# HV_Sense.net
KiCad netlist of a schematic drawn in Altium Designer
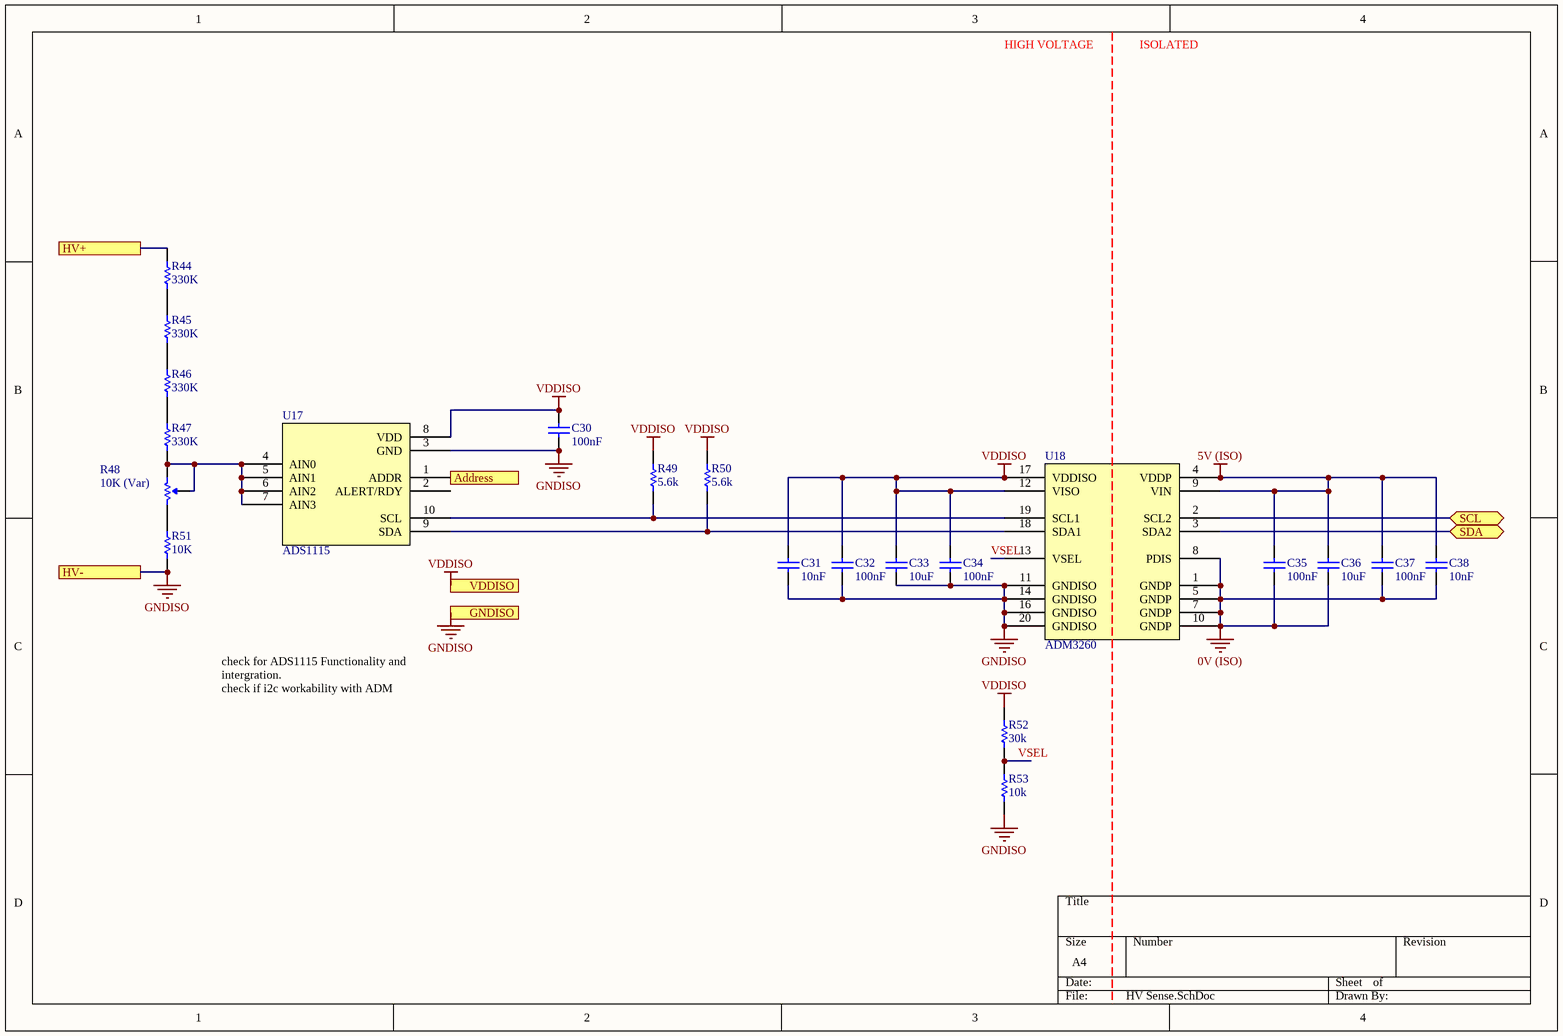
[diagram p0: HV Sense.SchDoc]

(export (version "E")
  (design (tool "Eeschema 10.0.6"))
  (components
    (comp (ref "C30")
      (value "100nF")
      (footprint "0805")
      (fields
        (field (name "PART NUMBER") "GCM21BR71H104KA37L")
        (field (name "TOLERANCE") "±10%")
        (field (name "MANUFACTURER") "muRata")
      )
      (libsource (lib "ts_20-standard-library") (part "Capacitor"))
    )
    (comp (ref "C31")
      (value "10nF")
      (footprint "0805")
      (fields
        (field (name "PART NUMBER") "GCM2195C1H103JA16D")
        (field (name "TOLERANCE") "±5%")
        (field (name "MANUFACTURER") "muRata")
      )
      (libsource (lib "ts_20-standard-library") (part "Capacitor"))
    )
    (comp (ref "C32")
      (value "100nF")
      (footprint "0805")
      (fields
        (field (name "PART NUMBER") "GCM21BR71H104KA37L")
        (field (name "TOLERANCE") "±10%")
        (field (name "MANUFACTURER") "muRata")
      )
      (libsource (lib "ts_20-standard-library") (part "Capacitor"))
    )
    (comp (ref "C33")
      (value "10uF")
      (footprint "0805")
      (fields
        (field (name "PART NUMBER") "GRM21BR6YA106KE43L")
        (field (name "TOLERANCE") "10%")
        (field (name "MANUFACTURER") "muRata")
      )
      (libsource (lib "ts_20-standard-library") (part "Capacitor"))
    )
    (comp (ref "C34")
      (value "100nF")
      (footprint "0805")
      (fields
        (field (name "PART NUMBER") "GCM21BR71H104KA37L")
        (field (name "TOLERANCE") "±10%")
        (field (name "MANUFACTURER") "muRata")
      )
      (libsource (lib "ts_20-standard-library") (part "Capacitor"))
    )
    (comp (ref "C35")
      (value "100nF")
      (footprint "0805")
      (fields
        (field (name "PART NUMBER") "GCM21BR71H104KA37L")
        (field (name "TOLERANCE") "±10%")
        (field (name "MANUFACTURER") "muRata")
      )
      (libsource (lib "ts_20-standard-library") (part "Capacitor"))
    )
    (comp (ref "C36")
      (value "10uF")
      (footprint "0805")
      (fields
        (field (name "PART NUMBER") "GRM21BR6YA106KE43L")
        (field (name "TOLERANCE") "10%")
        (field (name "MANUFACTURER") "muRata")
      )
      (libsource (lib "ts_20-standard-library") (part "Capacitor"))
    )
    (comp (ref "C37")
      (value "100nF")
      (footprint "0805")
      (fields
        (field (name "PART NUMBER") "GCM21BR71H104KA37L")
        (field (name "TOLERANCE") "±10%")
        (field (name "MANUFACTURER") "muRata")
      )
      (libsource (lib "ts_20-standard-library") (part "Capacitor"))
    )
    (comp (ref "C38")
      (value "10nF")
      (footprint "0805")
      (fields
        (field (name "PART NUMBER") "GCM2195C1H103JA16D")
        (field (name "TOLERANCE") "±5%")
        (field (name "MANUFACTURER") "muRata")
      )
      (libsource (lib "ts_20-standard-library") (part "Capacitor"))
    )
    (comp (ref "R44")
      (value "330K")
      (footprint "VB 0204")
      (fields
        (field (name "PART NUMBER") "MMA02040C3303FB300")
        (field (name "MANUFACTURER") "Vishay Beyschlag")
        (field (name "TOLERANCE") "0.01")
      )
      (libsource (lib "ts_20-standard-library") (part "Resistor"))
    )
    (comp (ref "R45")
      (value "330K")
      (footprint "VB 0204")
      (fields
        (field (name "PART NUMBER") "MMA02040C3303FB300")
        (field (name "MANUFACTURER") "Vishay Beyschlag")
        (field (name "TOLERANCE") "0.01")
      )
      (libsource (lib "ts_20-standard-library") (part "Resistor"))
    )
    (comp (ref "R46")
      (value "330K")
      (footprint "VB 0204")
      (fields
        (field (name "PART NUMBER") "MMA02040C3303FB300")
        (field (name "MANUFACTURER") "Vishay Beyschlag")
        (field (name "TOLERANCE") "0.01")
      )
      (libsource (lib "ts_20-standard-library") (part "Resistor"))
    )
    (comp (ref "R47")
      (value "330K")
      (footprint "VB 0204")
      (fields
        (field (name "PART NUMBER") "MMA02040C3303FB300")
        (field (name "MANUFACTURER") "Vishay Beyschlag")
        (field (name "TOLERANCE") "0.01")
      )
      (libsource (lib "ts_20-standard-library") (part "Resistor"))
    )
    (comp (ref "R48")
      (value "10K (Var)")
      (footprint "B 3296")
      (fields
        (field (name "PART NUMBER") "3296W-1-103LF")
        (field (name "MANUFACTURER") "Bournes Inc")
        (field (name "TOLERANCE") "0.1")
      )
      (libsource (lib "ts_20-standard-library") (part "Resistor (Potentiometer)"))
    )
    (comp (ref "R49")
      (value "5.6k")
      (footprint "0805")
      (fields
        (field (name "PART NUMBER") "RC0805FR075K6L")
        (field (name "MANUFACTURER") "YAGEO")
        (field (name "TOLERANCE") "0.01")
      )
      (libsource (lib "ts_20-standard-library") (part "Resistor"))
    )
    (comp (ref "R50")
      (value "5.6k")
      (footprint "0805")
      (fields
        (field (name "PART NUMBER") "RC0805FR075K6L")
        (field (name "MANUFACTURER") "YAGEO")
        (field (name "TOLERANCE") "0.01")
      )
      (libsource (lib "ts_20-standard-library") (part "Resistor"))
    )
    (comp (ref "R51")
      (value "10K")
      (footprint "VB 0204")
      (fields
        (field (name "PART NUMBER") "MMA02040C1002FB300")
        (field (name "MANUFACTURER") "Vishay Beyschlag")
        (field (name "TOLERANCE") "0.01")
      )
      (libsource (lib "ts_20-standard-library") (part "Resistor"))
    )
    (comp (ref "R52")
      (value "30k")
      (footprint "0805")
      (fields
        (field (name "PART NUMBER") "RC0805FR0730KL")
        (field (name "MANUFACTURER") "YAGEO")
        (field (name "TOLERANCE") "0.01")
      )
      (libsource (lib "ts_20-standard-library") (part "Resistor"))
    )
    (comp (ref "R53")
      (value "10k")
      (footprint "0805")
      (fields
        (field (name "PART NUMBER") "RC0805FR0710KL")
        (field (name "MANUFACTURER") "YAGEO")
        (field (name "TOLERANCE") "0.01")
      )
      (libsource (lib "ts_20-standard-library") (part "Resistor"))
    )
    (comp (ref "U17")
      (value "ADS1115")
      (footprint "TI 10-VSSOP")
      (description "16 Bit Analog to Digital Converter 2, 4 Input 1 Sigma-Delta 10-VSSOP")
      (fields
        (field (name "MANUFACTURER") "Texas Instruments")
        (field (name "DIGIKEY PART NUMBER") "296-38849-1-ND")
      )
      (libsource (lib "ts_20-standard-library") (part "ADS1115"))
    )
    (comp (ref "U18")
      (value "ADM3260")
      (footprint "AD 20-SSOP")
      (description "I²C Digital Isolator 2500Vrms 2 Channel 25kV/µs CMTI 20-SSOP (0.209\", 5.30mm Width)")
      (fields
        (field (name "MANUFACTURER") "Analog Devices")
        (field (name "DIGIKEY PART NUMBER") "ADM3260ARSZ-RL7CT-ND")
      )
      (libsource (lib "ts_20-standard-library") (part "ADM3260"))
    )
  )
  (nets
    (net (code "1") (name "/Address") (class "Default")
      (node (ref "U17") (pin "1") (pinfunction "ADDR_1") (pintype "passive"))
    )
    (net (code "2") (name "/HV+") (class "Default")
      (node (ref "R44") (pin "2") (pinfunction "2_2") (pintype "passive"))
    )
    (net (code "3") (name "/SCL") (class "Default")
      (node (ref "U18") (pin "2") (pinfunction "SCL2_2") (pintype "passive"))
    )
    (net (code "4") (name "/SDA") (class "Default")
      (node (ref "U18") (pin "3") (pinfunction "SDA2_3") (pintype "passive"))
    )
    (net (code "5") (name "/VSEL") (class "Default")
      (node (ref "R52") (pin "1") (pinfunction "1_1") (pintype "passive"))
      (node (ref "R53") (pin "2") (pinfunction "2_2") (pintype "passive"))
      (node (ref "U18") (pin "13") (pinfunction "VSEL_13") (pintype "passive"))
    )
    (net (code "6") (name "0V (ISO)") (class "Default")
      (node (ref "C35") (pin "1") (pinfunction "1_1") (pintype "passive"))
      (node (ref "C36") (pin "1") (pinfunction "1_1") (pintype "passive"))
      (node (ref "C37") (pin "1") (pinfunction "1_1") (pintype "passive"))
      (node (ref "C38") (pin "1") (pinfunction "1_1") (pintype "passive"))
      (node (ref "U18") (pin "1") (pinfunction "GNDP_1") (pintype "passive"))
      (node (ref "U18") (pin "10") (pinfunction "GNDP_10") (pintype "passive"))
      (node (ref "U18") (pin "5") (pinfunction "GNDP_5") (pintype "passive"))
      (node (ref "U18") (pin "7") (pinfunction "GNDP_7") (pintype "passive"))
      (node (ref "U18") (pin "8") (pinfunction "PDIS_8") (pintype "passive"))
    )
    (net (code "7") (name "5V (ISO)") (class "Default")
      (node (ref "C35") (pin "2") (pinfunction "2_2") (pintype "passive"))
      (node (ref "C36") (pin "2") (pinfunction "2_2") (pintype "passive"))
      (node (ref "C37") (pin "2") (pinfunction "2_2") (pintype "passive"))
      (node (ref "C38") (pin "2") (pinfunction "2_2") (pintype "passive"))
      (node (ref "U18") (pin "4") (pinfunction "VDDP_4") (pintype "passive"))
      (node (ref "U18") (pin "9") (pinfunction "VIN_9") (pintype "passive"))
    )
    (net (code "8") (name "GNDISO") (class "Default")
      (node (ref "C30") (pin "2") (pinfunction "2_2") (pintype "passive"))
      (node (ref "C31") (pin "1") (pinfunction "1_1") (pintype "passive"))
      (node (ref "C32") (pin "1") (pinfunction "1_1") (pintype "passive"))
      (node (ref "C33") (pin "1") (pinfunction "1_1") (pintype "passive"))
      (node (ref "C34") (pin "2") (pinfunction "2_2") (pintype "passive"))
      (node (ref "R51") (pin "1") (pinfunction "1_1") (pintype "passive"))
      (node (ref "R53") (pin "1") (pinfunction "1_1") (pintype "passive"))
      (node (ref "U17") (pin "3") (pinfunction "GND_3") (pintype "passive"))
      (node (ref "U18") (pin "11") (pinfunction "GNDISO_11") (pintype "passive"))
      (node (ref "U18") (pin "14") (pinfunction "GNDISO_14") (pintype "passive"))
      (node (ref "U18") (pin "16") (pinfunction "GNDISO_16") (pintype "passive"))
      (node (ref "U18") (pin "20") (pinfunction "GNDISO_20") (pintype "passive"))
    )
    (net (code "9") (name "Net-(R44-Pad1)") (class "Default")
      (node (ref "R44") (pin "1") (pinfunction "1_1") (pintype "passive"))
      (node (ref "R45") (pin "2") (pinfunction "2_2") (pintype "passive"))
    )
    (net (code "10") (name "Net-(R45-Pad1)") (class "Default")
      (node (ref "R45") (pin "1") (pinfunction "1_1") (pintype "passive"))
      (node (ref "R46") (pin "2") (pinfunction "2_2") (pintype "passive"))
    )
    (net (code "11") (name "Net-(R46-Pad1)") (class "Default")
      (node (ref "R46") (pin "1") (pinfunction "1_1") (pintype "passive"))
      (node (ref "R47") (pin "2") (pinfunction "2_2") (pintype "passive"))
    )
    (net (code "12") (name "Net-(R48-CCW)") (class "Default")
      (node (ref "R48") (pin "1") (pinfunction "CCW_1") (pintype "passive"))
      (node (ref "R51") (pin "2") (pinfunction "2_2") (pintype "passive"))
    )
    (net (code "13") (name "Net-(R48-CW)") (class "Default")
      (node (ref "R47") (pin "1") (pinfunction "1_1") (pintype "passive"))
      (node (ref "R48") (pin "2") (pinfunction "Wiper_2") (pintype "passive"))
      (node (ref "R48") (pin "3") (pinfunction "CW_3") (pintype "passive"))
      (node (ref "U17") (pin "4") (pinfunction "AIN0_4") (pintype "passive"))
      (node (ref "U17") (pin "5") (pinfunction "AIN1_5") (pintype "passive"))
      (node (ref "U17") (pin "6") (pinfunction "AIN2_6") (pintype "passive"))
      (node (ref "U17") (pin "7") (pinfunction "AIN3_7") (pintype "passive"))
    )
    (net (code "14") (name "Net-(U17-SCL)") (class "Default")
      (node (ref "R49") (pin "1") (pinfunction "1_1") (pintype "passive"))
      (node (ref "U17") (pin "10") (pinfunction "SCL_10") (pintype "passive"))
      (node (ref "U18") (pin "19") (pinfunction "SCL1_19") (pintype "passive"))
    )
    (net (code "15") (name "Net-(U17-SDA)") (class "Default")
      (node (ref "R50") (pin "1") (pinfunction "1_1") (pintype "passive"))
      (node (ref "U17") (pin "9") (pinfunction "SDA_9") (pintype "passive"))
      (node (ref "U18") (pin "18") (pinfunction "SDA1_18") (pintype "passive"))
    )
    (net (code "16") (name "VDDISO") (class "Default")
      (node (ref "C30") (pin "1") (pinfunction "1_1") (pintype "passive"))
      (node (ref "C31") (pin "2") (pinfunction "2_2") (pintype "passive"))
      (node (ref "C32") (pin "2") (pinfunction "2_2") (pintype "passive"))
      (node (ref "C33") (pin "2") (pinfunction "2_2") (pintype "passive"))
      (node (ref "C34") (pin "1") (pinfunction "1_1") (pintype "passive"))
      (node (ref "R49") (pin "2") (pinfunction "2_2") (pintype "passive"))
      (node (ref "R50") (pin "2") (pinfunction "2_2") (pintype "passive"))
      (node (ref "R52") (pin "2") (pinfunction "2_2") (pintype "passive"))
      (node (ref "U17") (pin "8") (pinfunction "VDD_8") (pintype "passive"))
      (node (ref "U18") (pin "12") (pinfunction "VISO_12") (pintype "passive"))
      (node (ref "U18") (pin "17") (pinfunction "VDDISO_17") (pintype "passive"))
    )
    (net (code "17") (name "unconnected-(U17-ALERT{slash}RDY-Pad2)") (class "Default")
      (node (ref "U17") (pin "2") (pinfunction "ALERT/RDY_2") (pintype "passive"))
    )
  )
)
